# ninja_star.net
KiCad netlist of a schematic drawn in EAGLE
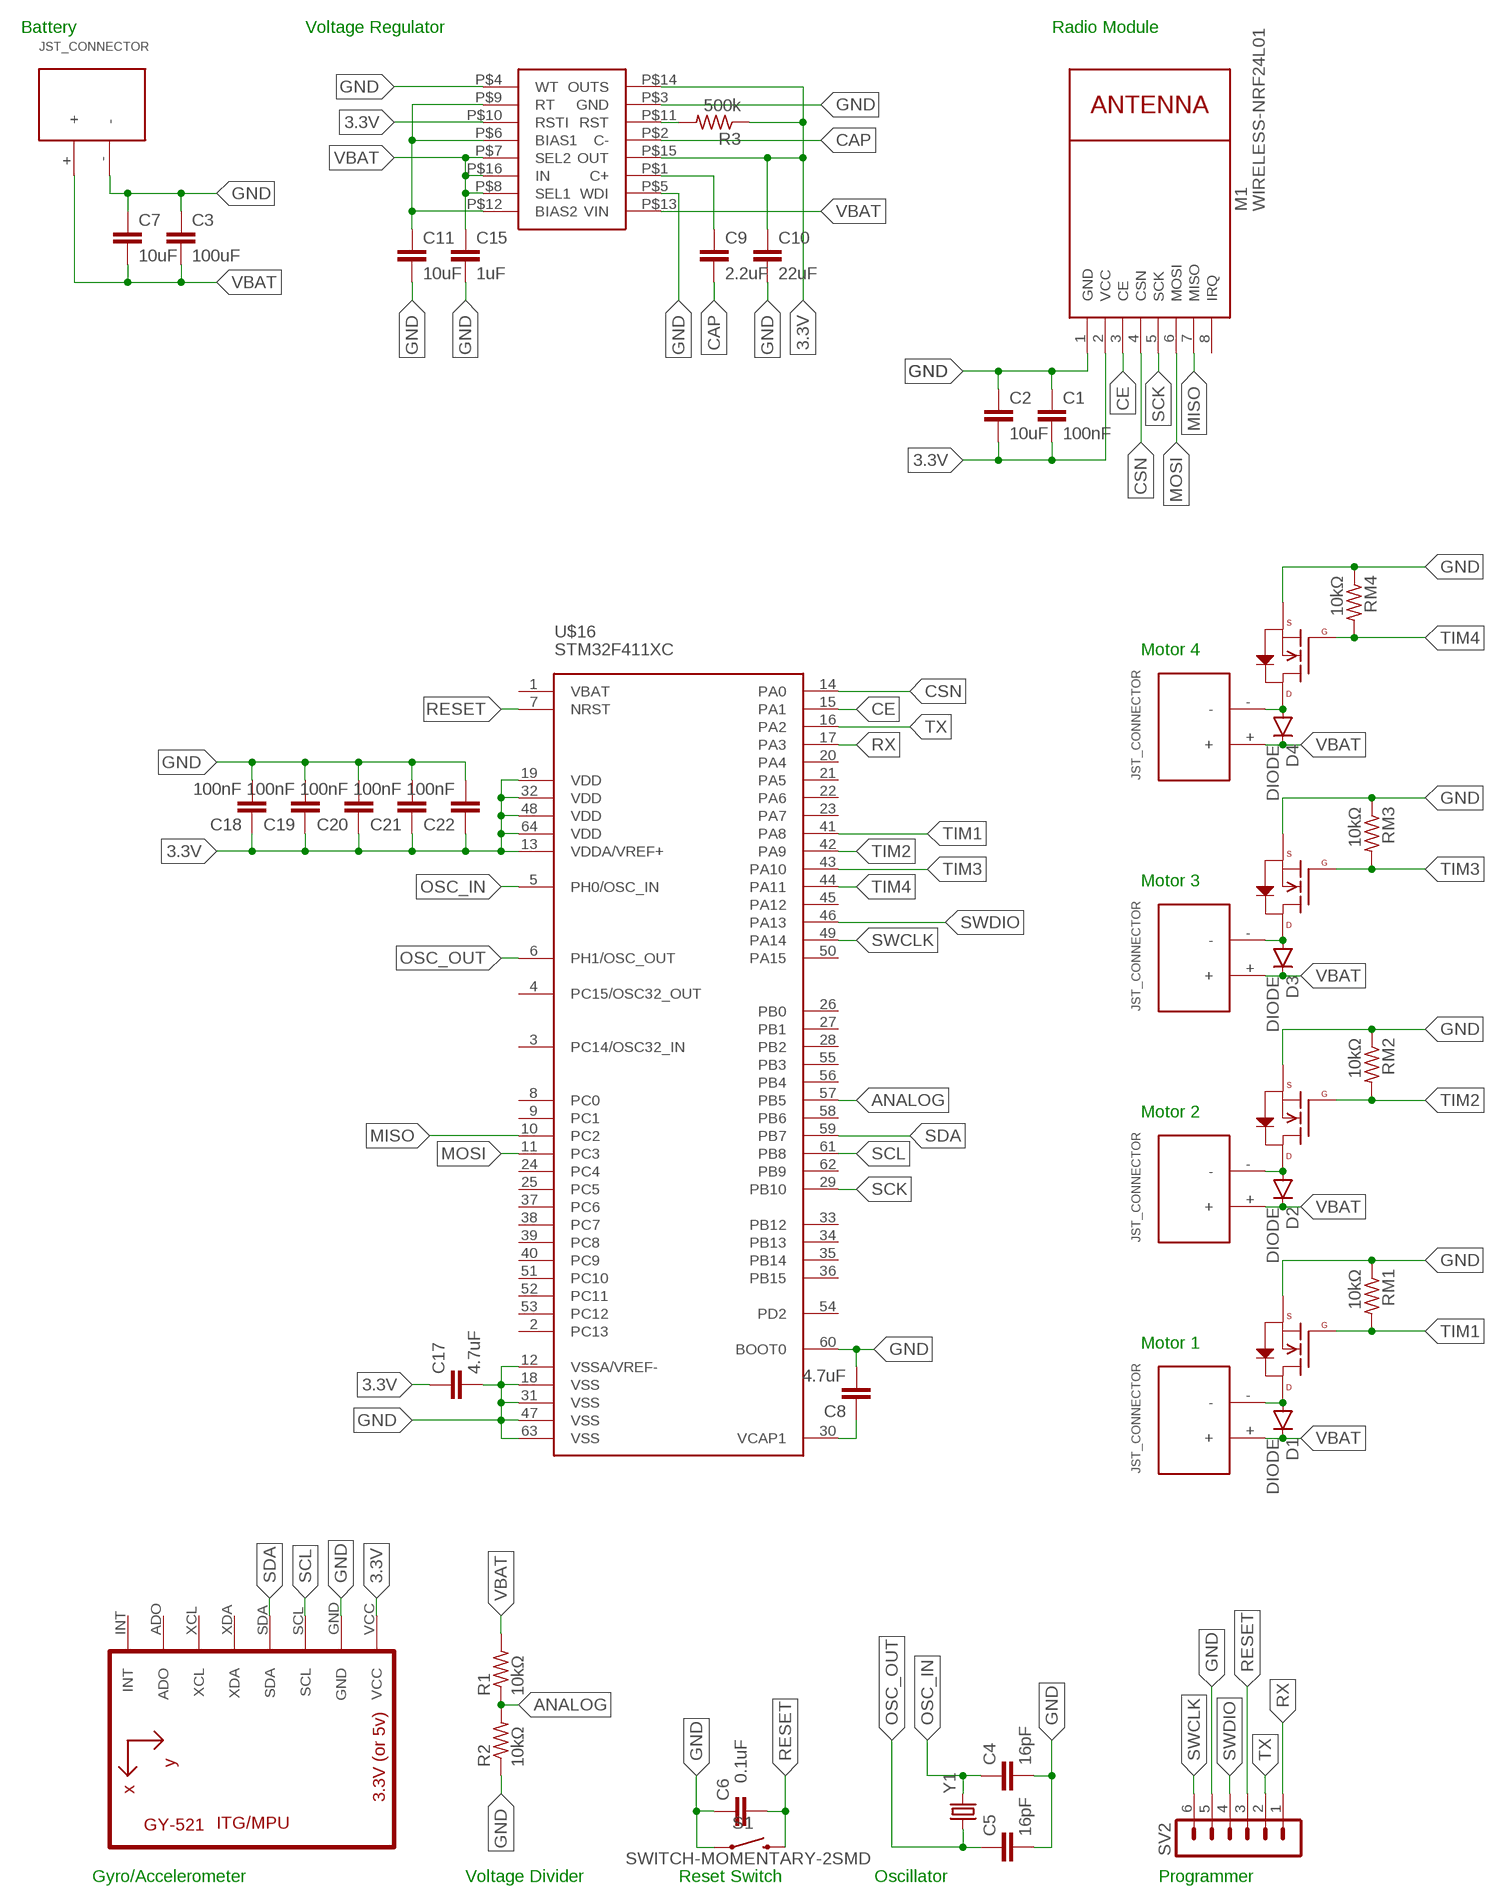
[diagram p0: schematic, sheet 1]

(export (version "E")
  (design (tool "Eeschema 10.0.6"))
  (components
    (comp (ref "C1")
      (value "100nF")
      (footprint "eagle-import:C0603")
      (libsource (lib "eagle-import") (part "C-EUC0603"))
    )
    (comp (ref "C2")
      (value "10uF")
      (footprint "eagle-import:C0603")
      (libsource (lib "eagle-import") (part "C-EUC0603"))
    )
    (comp (ref "C3")
      (value "100uF")
      (footprint "eagle-import:C1206")
      (libsource (lib "eagle-import") (part "C-EUC1206"))
    )
    (comp (ref "C4")
      (value "16pF")
      (footprint "eagle-import:C0603")
      (libsource (lib "eagle-import") (part "C-EUC0603"))
    )
    (comp (ref "C5")
      (value "16pF")
      (footprint "eagle-import:C0603")
      (libsource (lib "eagle-import") (part "C-EUC0603"))
    )
    (comp (ref "C6")
      (value "0.1uF")
      (footprint "eagle-import:C0603")
      (libsource (lib "eagle-import") (part "C-EUC0603"))
    )
    (comp (ref "C7")
      (value "10uF")
      (footprint "eagle-import:C0603")
      (libsource (lib "eagle-import") (part "C-EUC0603"))
    )
    (comp (ref "C8")
      (value "4.7uF")
      (footprint "eagle-import:C0603")
      (libsource (lib "eagle-import") (part "C-EUC0603"))
    )
    (comp (ref "C9")
      (value "2.2uF")
      (footprint "eagle-import:C0603")
      (libsource (lib "eagle-import") (part "C-EUC0603"))
    )
    (comp (ref "C10")
      (value "22uF")
      (footprint "eagle-import:C0603")
      (libsource (lib "eagle-import") (part "C-EUC0603"))
    )
    (comp (ref "C11")
      (value "10uF")
      (footprint "eagle-import:C0603")
      (libsource (lib "eagle-import") (part "C-EUC0603"))
    )
    (comp (ref "C15")
      (value "1uF")
      (footprint "eagle-import:C0603")
      (libsource (lib "eagle-import") (part "C-EUC0603"))
    )
    (comp (ref "C17")
      (value "4.7uF")
      (footprint "eagle-import:C0603")
      (libsource (lib "eagle-import") (part "C-EUC0603"))
    )
    (comp (ref "C18")
      (value "100nF")
      (footprint "eagle-import:C0603")
      (libsource (lib "eagle-import") (part "C-EUC0603"))
    )
    (comp (ref "C19")
      (value "100nF")
      (footprint "eagle-import:C0603")
      (libsource (lib "eagle-import") (part "C-EUC0603"))
    )
    (comp (ref "C20")
      (value "100nF")
      (footprint "eagle-import:C0603")
      (libsource (lib "eagle-import") (part "C-EUC0603"))
    )
    (comp (ref "C21")
      (value "100nF")
      (footprint "eagle-import:C0603")
      (libsource (lib "eagle-import") (part "C-EUC0603"))
    )
    (comp (ref "C22")
      (value "100nF")
      (footprint "eagle-import:C0603")
      (libsource (lib "eagle-import") (part "C-EUC0603"))
    )
    (comp (ref "D1")
      (value "DIODE")
      (footprint "eagle-import:C0603")
      (libsource (lib "eagle-import") (part "DIODE"))
    )
    (comp (ref "D2")
      (value "DIODE")
      (footprint "eagle-import:C0603")
      (libsource (lib "eagle-import") (part "DIODE"))
    )
    (comp (ref "D3")
      (value "DIODE")
      (footprint "eagle-import:C0603")
      (libsource (lib "eagle-import") (part "DIODE"))
    )
    (comp (ref "D4")
      (value "DIODE")
      (footprint "eagle-import:C0603")
      (libsource (lib "eagle-import") (part "DIODE"))
    )
    (comp (ref "M1")
      (value "WIRELESS-NRF24L01")
      (footprint "eagle-import:WIRELESS-NRF24L01")
      (libsource (lib "eagle-import") (part "WIRELESS-NRF24L01"))
    )
    (comp (ref "MOS1")
      (value "N-CHANNEL-MOSFET-IRLML6244TRPBF")
      (footprint "eagle-import:SOT23-3")
      (libsource (lib "eagle-import") (part "N-CHANNEL-MOSFET-IRLML6244TRPBF"))
    )
    (comp (ref "MOS2")
      (value "N-CHANNEL-MOSFET-IRLML6244TRPBF")
      (footprint "eagle-import:SOT23-3")
      (libsource (lib "eagle-import") (part "N-CHANNEL-MOSFET-IRLML6244TRPBF"))
    )
    (comp (ref "MOS3")
      (value "N-CHANNEL-MOSFET-IRLML6244TRPBF")
      (footprint "eagle-import:SOT23-3")
      (libsource (lib "eagle-import") (part "N-CHANNEL-MOSFET-IRLML6244TRPBF"))
    )
    (comp (ref "MOS4")
      (value "N-CHANNEL-MOSFET-IRLML6244TRPBF")
      (footprint "eagle-import:SOT23-3")
      (libsource (lib "eagle-import") (part "N-CHANNEL-MOSFET-IRLML6244TRPBF"))
    )
    (comp (ref "MOTOR1")
      (value "JST_CONNECTOR_FEMALE")
      (footprint "eagle-import:JST_CONNECTOR_FEMALE")
      (libsource (lib "eagle-import") (part "JST_CONNECTOR_FEMALE"))
    )
    (comp (ref "MOTOR2")
      (value "JST_CONNECTOR_FEMALE")
      (footprint "eagle-import:JST_CONNECTOR_FEMALE")
      (libsource (lib "eagle-import") (part "JST_CONNECTOR_FEMALE"))
    )
    (comp (ref "MOTOR3")
      (value "JST_CONNECTOR_FEMALE")
      (footprint "eagle-import:JST_CONNECTOR_FEMALE")
      (libsource (lib "eagle-import") (part "JST_CONNECTOR_FEMALE"))
    )
    (comp (ref "MOTOR4")
      (value "JST_CONNECTOR_FEMALE")
      (footprint "eagle-import:JST_CONNECTOR_FEMALE")
      (libsource (lib "eagle-import") (part "JST_CONNECTOR_FEMALE"))
    )
    (comp (ref "R1")
      (value "10kΩ")
      (footprint "eagle-import:R0603")
      (libsource (lib "eagle-import") (part "R-US_R0603"))
    )
    (comp (ref "R2")
      (value "10kΩ")
      (footprint "eagle-import:R0603")
      (libsource (lib "eagle-import") (part "R-US_R0603"))
    )
    (comp (ref "R3")
      (value "500k")
      (footprint "eagle-import:R0603")
      (libsource (lib "eagle-import") (part "R-0603"))
    )
    (comp (ref "RM1")
      (value "10kΩ")
      (footprint "eagle-import:R0603")
      (libsource (lib "eagle-import") (part "AP_quad_updated_R-0603"))
    )
    (comp (ref "RM2")
      (value "10kΩ")
      (footprint "eagle-import:R0603")
      (libsource (lib "eagle-import") (part "AP_quad_updated_R-0603"))
    )
    (comp (ref "RM3")
      (value "10kΩ")
      (footprint "eagle-import:R0603")
      (libsource (lib "eagle-import") (part "AP_quad_updated_R-0603"))
    )
    (comp (ref "RM4")
      (value "10kΩ")
      (footprint "eagle-import:R0603")
      (libsource (lib "eagle-import") (part "AP_quad_updated_R-0603"))
    )
    (comp (ref "S1")
      (value "SWITCH-MOMENTARY-2SMD")
      (footprint "eagle-import:TACTILE-SWITCH-SMD")
      (libsource (lib "eagle-import") (part "SWITCH-MOMENTARY-2SMD"))
    )
    (comp (ref "SV2")
      (value "MA06-1")
      (footprint "eagle-import:MA06-1")
      (libsource (lib "eagle-import") (part "MA06-1"))
    )
    (comp (ref "U$7")
      (value "JST_CONNECTOR_FEMALE")
      (footprint "eagle-import:JST_CONNECTOR_FEMALE")
      (libsource (lib "eagle-import") (part "JST_CONNECTOR_FEMALE"))
    )
    (comp (ref "U$12")
      (value "VR-LTC3246")
      (footprint "eagle-import:MSOP-16")
      (libsource (lib "eagle-import") (part "VR-LTC3246"))
    )
    (comp (ref "U$16")
      (value "STM32F411XC")
      (footprint "eagle-import:LQFP64")
      (libsource (lib "eagle-import") (part "STM32F411XC"))
    )
    (comp (ref "U1")
      (value "GY-521MPU6050")
      (footprint "eagle-import:GY-521")
      (libsource (lib "eagle-import") (part "GY-521MPU6050"))
    )
    (comp (ref "Y1")
      (value "CRYSTALHC49US")
      (footprint "eagle-import:HC49US")
      (libsource (lib "eagle-import") (part "CRYSTALHC49US"))
    )
  )
  (nets
    (net (code "1") (name "3.3V") (class "Default")
      (node (ref "C1") (pin "2") (pinfunction "2_2") (pintype "passive"))
      (node (ref "C10") (pin "1") (pinfunction "1_1") (pintype "passive"))
      (node (ref "C17") (pin "1") (pinfunction "1_1") (pintype "passive"))
      (node (ref "C18") (pin "1") (pinfunction "1_1") (pintype "passive"))
      (node (ref "C19") (pin "1") (pinfunction "1_1") (pintype "passive"))
      (node (ref "C2") (pin "2") (pinfunction "2_2") (pintype "passive"))
      (node (ref "C20") (pin "1") (pinfunction "1_1") (pintype "passive"))
      (node (ref "C21") (pin "1") (pinfunction "1_1") (pintype "passive"))
      (node (ref "C22") (pin "1") (pinfunction "1_1") (pintype "passive"))
      (node (ref "M1") (pin "2") (pinfunction "VCC_2") (pintype "power_in"))
      (node (ref "R3") (pin "1") (pinfunction "1_1") (pintype "passive"))
      (node (ref "U$12") (pin "P$10") (pinfunction "RSTI_P$10") (pintype "bidirectional"))
      (node (ref "U$12") (pin "P$14") (pinfunction "OUTS_P$14") (pintype "bidirectional"))
      (node (ref "U$12") (pin "P$15") (pinfunction "OUT_P$15") (pintype "bidirectional"))
      (node (ref "U$16") (pin "13") (pinfunction "VDDA/VREF+_13") (pintype "bidirectional"))
      (node (ref "U$16") (pin "19") (pinfunction "VDD_19") (pintype "bidirectional"))
      (node (ref "U$16") (pin "32") (pinfunction "VDD_32") (pintype "bidirectional"))
      (node (ref "U$16") (pin "48") (pinfunction "VDD_48") (pintype "bidirectional"))
      (node (ref "U$16") (pin "64") (pinfunction "VDD_64") (pintype "bidirectional"))
      (node (ref "U1") (pin "VCC") (pinfunction "VCC_VCC") (pintype "bidirectional"))
    )
    (net (code "2") (name "ANALOG") (class "Default")
      (node (ref "R1") (pin "1") (pinfunction "1_1") (pintype "passive"))
      (node (ref "R2") (pin "2") (pinfunction "2_2") (pintype "passive"))
      (node (ref "U$16") (pin "57") (pinfunction "PB5_57") (pintype "bidirectional"))
    )
    (net (code "3") (name "CAP") (class "Default")
      (node (ref "C9") (pin "2") (pinfunction "2_2") (pintype "passive"))
      (node (ref "U$12") (pin "P$2") (pinfunction "C-_P$2") (pintype "bidirectional"))
    )
    (net (code "4") (name "CE") (class "Default")
      (node (ref "M1") (pin "3") (pinfunction "CE_3") (pintype "bidirectional"))
      (node (ref "U$16") (pin "15") (pinfunction "PA1_15") (pintype "bidirectional"))
    )
    (net (code "5") (name "CSN") (class "Default")
      (node (ref "M1") (pin "4") (pinfunction "CSN_4") (pintype "bidirectional"))
      (node (ref "U$16") (pin "14") (pinfunction "PA0_14") (pintype "bidirectional"))
    )
    (net (code "6") (name "GND") (class "Default")
      (node (ref "C1") (pin "1") (pinfunction "1_1") (pintype "passive"))
      (node (ref "C10") (pin "2") (pinfunction "2_2") (pintype "passive"))
      (node (ref "C11") (pin "2") (pinfunction "2_2") (pintype "passive"))
      (node (ref "C15") (pin "2") (pinfunction "2_2") (pintype "passive"))
      (node (ref "C17") (pin "2") (pinfunction "2_2") (pintype "passive"))
      (node (ref "C18") (pin "2") (pinfunction "2_2") (pintype "passive"))
      (node (ref "C19") (pin "2") (pinfunction "2_2") (pintype "passive"))
      (node (ref "C2") (pin "1") (pinfunction "1_1") (pintype "passive"))
      (node (ref "C20") (pin "2") (pinfunction "2_2") (pintype "passive"))
      (node (ref "C21") (pin "2") (pinfunction "2_2") (pintype "passive"))
      (node (ref "C22") (pin "2") (pinfunction "2_2") (pintype "passive"))
      (node (ref "C3") (pin "1") (pinfunction "1_1") (pintype "passive"))
      (node (ref "C4") (pin "2") (pinfunction "2_2") (pintype "passive"))
      (node (ref "C5") (pin "2") (pinfunction "2_2") (pintype "passive"))
      (node (ref "C6") (pin "1") (pinfunction "1_1") (pintype "passive"))
      (node (ref "C7") (pin "1") (pinfunction "1_1") (pintype "passive"))
      (node (ref "C8") (pin "2") (pinfunction "2_2") (pintype "passive"))
      (node (ref "M1") (pin "1") (pinfunction "GND_1") (pintype "power_in"))
      (node (ref "MOS1") (pin "2") (pinfunction "S_2") (pintype "passive"))
      (node (ref "MOS2") (pin "2") (pinfunction "S_2") (pintype "passive"))
      (node (ref "MOS3") (pin "2") (pinfunction "S_2") (pintype "passive"))
      (node (ref "MOS4") (pin "2") (pinfunction "S_2") (pintype "passive"))
      (node (ref "R2") (pin "1") (pinfunction "1_1") (pintype "passive"))
      (node (ref "RM1") (pin "1") (pinfunction "1_1") (pintype "passive"))
      (node (ref "RM2") (pin "1") (pinfunction "1_1") (pintype "passive"))
      (node (ref "RM3") (pin "1") (pinfunction "1_1") (pintype "passive"))
      (node (ref "RM4") (pin "1") (pinfunction "1_1") (pintype "passive"))
      (node (ref "S1") (pin "1") (pinfunction "1_1") (pintype "passive"))
      (node (ref "SV2") (pin "5") (pinfunction "5_5") (pintype "passive"))
      (node (ref "U$12") (pin "P$3") (pinfunction "GND_P$3") (pintype "bidirectional"))
      (node (ref "U$12") (pin "P$4") (pinfunction "WT_P$4") (pintype "bidirectional"))
      (node (ref "U$12") (pin "P$5") (pinfunction "WDI_P$5") (pintype "bidirectional"))
      (node (ref "U$16") (pin "12") (pinfunction "VSSA/VREF-_12") (pintype "bidirectional"))
      (node (ref "U$16") (pin "18") (pinfunction "VSS_18") (pintype "bidirectional"))
      (node (ref "U$16") (pin "31") (pinfunction "VSS_31") (pintype "bidirectional"))
      (node (ref "U$16") (pin "47") (pinfunction "VSS_47") (pintype "bidirectional"))
      (node (ref "U$16") (pin "60") (pinfunction "BOOT0_60") (pintype "bidirectional"))
      (node (ref "U$16") (pin "63") (pinfunction "VSS_63") (pintype "bidirectional"))
      (node (ref "U$7") (pin "-") (pinfunction "-_-") (pintype "bidirectional"))
      (node (ref "U1") (pin "GND") (pinfunction "GND_GND") (pintype "bidirectional"))
    )
    (net (code "7") (name "MISO") (class "Default")
      (node (ref "M1") (pin "7") (pinfunction "MISO_7") (pintype "bidirectional"))
      (node (ref "U$16") (pin "10") (pinfunction "PC2_10") (pintype "bidirectional"))
    )
    (net (code "8") (name "MOSI") (class "Default")
      (node (ref "M1") (pin "6") (pinfunction "MOSI_6") (pintype "bidirectional"))
      (node (ref "U$16") (pin "11") (pinfunction "PC3_11") (pintype "bidirectional"))
    )
    (net (code "9") (name "Net-(D1-PPIN)") (class "Default")
      (node (ref "D1") (pin "2") (pinfunction "PPIN_2") (pintype "passive"))
      (node (ref "MOS1") (pin "3") (pinfunction "D_3") (pintype "passive"))
      (node (ref "MOTOR1") (pin "-") (pinfunction "-_-") (pintype "bidirectional"))
    )
    (net (code "10") (name "Net-(D2-PPIN)") (class "Default")
      (node (ref "D2") (pin "2") (pinfunction "PPIN_2") (pintype "passive"))
      (node (ref "MOS2") (pin "3") (pinfunction "D_3") (pintype "passive"))
      (node (ref "MOTOR2") (pin "-") (pinfunction "-_-") (pintype "bidirectional"))
    )
    (net (code "11") (name "Net-(D3-PPIN)") (class "Default")
      (node (ref "D3") (pin "2") (pinfunction "PPIN_2") (pintype "passive"))
      (node (ref "MOS3") (pin "3") (pinfunction "D_3") (pintype "passive"))
      (node (ref "MOTOR3") (pin "-") (pinfunction "-_-") (pintype "bidirectional"))
    )
    (net (code "12") (name "Net-(D4-PPIN)") (class "Default")
      (node (ref "D4") (pin "2") (pinfunction "PPIN_2") (pintype "passive"))
      (node (ref "MOS4") (pin "3") (pinfunction "D_3") (pintype "passive"))
      (node (ref "MOTOR4") (pin "-") (pinfunction "-_-") (pintype "bidirectional"))
    )
    (net (code "13") (name "Net-(U$12-BIAS1)") (class "Default")
      (node (ref "C11") (pin "1") (pinfunction "1_1") (pintype "passive"))
      (node (ref "U$12") (pin "P$12") (pinfunction "BIAS2_P$12") (pintype "bidirectional"))
      (node (ref "U$12") (pin "P$6") (pinfunction "BIAS1_P$6") (pintype "bidirectional"))
      (node (ref "U$12") (pin "P$9") (pinfunction "RT_P$9") (pintype "bidirectional"))
    )
    (net (code "14") (name "Net-(U$12-C+)") (class "Default")
      (node (ref "C9") (pin "1") (pinfunction "1_1") (pintype "passive"))
      (node (ref "U$12") (pin "P$1") (pinfunction "C+_P$1") (pintype "bidirectional"))
    )
    (net (code "15") (name "Net-(U$12-RST)") (class "Default")
      (node (ref "R3") (pin "2") (pinfunction "2_2") (pintype "passive"))
      (node (ref "U$12") (pin "P$11") (pinfunction "RST_P$11") (pintype "bidirectional"))
    )
    (net (code "16") (name "Net-(U$16-VCAP1)") (class "Default")
      (node (ref "C8") (pin "1") (pinfunction "1_1") (pintype "passive"))
      (node (ref "U$16") (pin "30") (pinfunction "VCAP1_30") (pintype "bidirectional"))
    )
    (net (code "17") (name "OSC_IN") (class "Default")
      (node (ref "C4") (pin "1") (pinfunction "1_1") (pintype "passive"))
      (node (ref "U$16") (pin "5") (pinfunction "PH0/OSC_IN_5") (pintype "bidirectional"))
      (node (ref "Y1") (pin "2") (pinfunction "2_2") (pintype "passive"))
    )
    (net (code "18") (name "OSC_OUT") (class "Default")
      (node (ref "C5") (pin "1") (pinfunction "1_1") (pintype "passive"))
      (node (ref "U$16") (pin "6") (pinfunction "PH1/OSC_OUT_6") (pintype "bidirectional"))
      (node (ref "Y1") (pin "1") (pinfunction "1_1") (pintype "passive"))
    )
    (net (code "19") (name "RESET") (class "Default")
      (node (ref "C6") (pin "2") (pinfunction "2_2") (pintype "passive"))
      (node (ref "S1") (pin "3") (pinfunction "2_3") (pintype "passive"))
      (node (ref "SV2") (pin "3") (pinfunction "3_3") (pintype "passive"))
      (node (ref "U$16") (pin "7") (pinfunction "NRST_7") (pintype "bidirectional"))
    )
    (net (code "20") (name "RX") (class "Default")
      (node (ref "SV2") (pin "1") (pinfunction "1_1") (pintype "passive"))
      (node (ref "U$16") (pin "17") (pinfunction "PA3_17") (pintype "bidirectional"))
    )
    (net (code "21") (name "SCK") (class "Default")
      (node (ref "M1") (pin "5") (pinfunction "SCK_5") (pintype "bidirectional"))
      (node (ref "U$16") (pin "29") (pinfunction "PB10_29") (pintype "bidirectional"))
    )
    (net (code "22") (name "SCL") (class "Default")
      (node (ref "U$16") (pin "61") (pinfunction "PB8_61") (pintype "bidirectional"))
      (node (ref "U1") (pin "SCL") (pinfunction "SCL_SCL") (pintype "bidirectional"))
    )
    (net (code "23") (name "SDA") (class "Default")
      (node (ref "U$16") (pin "59") (pinfunction "PB7_59") (pintype "bidirectional"))
      (node (ref "U1") (pin "SDA") (pinfunction "SDA_SDA") (pintype "bidirectional"))
    )
    (net (code "24") (name "SWCLK") (class "Default")
      (node (ref "SV2") (pin "6") (pinfunction "6_6") (pintype "passive"))
      (node (ref "U$16") (pin "49") (pinfunction "PA14_49") (pintype "bidirectional"))
    )
    (net (code "25") (name "SWDIO") (class "Default")
      (node (ref "SV2") (pin "4") (pinfunction "4_4") (pintype "passive"))
      (node (ref "U$16") (pin "46") (pinfunction "PA13_46") (pintype "bidirectional"))
    )
    (net (code "26") (name "TIM1") (class "Default")
      (node (ref "MOS1") (pin "1") (pinfunction "G_1") (pintype "passive"))
      (node (ref "RM1") (pin "2") (pinfunction "2_2") (pintype "passive"))
      (node (ref "U$16") (pin "41") (pinfunction "PA8_41") (pintype "bidirectional"))
    )
    (net (code "27") (name "TIM2") (class "Default")
      (node (ref "MOS2") (pin "1") (pinfunction "G_1") (pintype "passive"))
      (node (ref "RM2") (pin "2") (pinfunction "2_2") (pintype "passive"))
      (node (ref "U$16") (pin "42") (pinfunction "PA9_42") (pintype "bidirectional"))
    )
    (net (code "28") (name "TIM3") (class "Default")
      (node (ref "MOS3") (pin "1") (pinfunction "G_1") (pintype "passive"))
      (node (ref "RM3") (pin "2") (pinfunction "2_2") (pintype "passive"))
      (node (ref "U$16") (pin "43") (pinfunction "PA10_43") (pintype "bidirectional"))
    )
    (net (code "29") (name "TIM4") (class "Default")
      (node (ref "MOS4") (pin "1") (pinfunction "G_1") (pintype "passive"))
      (node (ref "RM4") (pin "2") (pinfunction "2_2") (pintype "passive"))
      (node (ref "U$16") (pin "44") (pinfunction "PA11_44") (pintype "bidirectional"))
    )
    (net (code "30") (name "TX") (class "Default")
      (node (ref "SV2") (pin "2") (pinfunction "2_2") (pintype "passive"))
      (node (ref "U$16") (pin "16") (pinfunction "PA2_16") (pintype "bidirectional"))
    )
    (net (code "31") (name "VBAT") (class "Default")
      (node (ref "C15") (pin "1") (pinfunction "1_1") (pintype "passive"))
      (node (ref "C3") (pin "2") (pinfunction "2_2") (pintype "passive"))
      (node (ref "C7") (pin "2") (pinfunction "2_2") (pintype "passive"))
      (node (ref "D1") (pin "1") (pinfunction "GPIN_1") (pintype "passive"))
      (node (ref "D2") (pin "1") (pinfunction "GPIN_1") (pintype "passive"))
      (node (ref "D3") (pin "1") (pinfunction "GPIN_1") (pintype "passive"))
      (node (ref "D4") (pin "1") (pinfunction "GPIN_1") (pintype "passive"))
      (node (ref "MOTOR1") (pin "+") (pinfunction "+_+") (pintype "bidirectional"))
      (node (ref "MOTOR2") (pin "+") (pinfunction "+_+") (pintype "bidirectional"))
      (node (ref "MOTOR3") (pin "+") (pinfunction "+_+") (pintype "bidirectional"))
      (node (ref "MOTOR4") (pin "+") (pinfunction "+_+") (pintype "bidirectional"))
      (node (ref "R1") (pin "2") (pinfunction "2_2") (pintype "passive"))
      (node (ref "U$12") (pin "P$13") (pinfunction "VIN_P$13") (pintype "bidirectional"))
      (node (ref "U$12") (pin "P$16") (pinfunction "IN_P$16") (pintype "bidirectional"))
      (node (ref "U$12") (pin "P$7") (pinfunction "SEL2_P$7") (pintype "bidirectional"))
      (node (ref "U$12") (pin "P$8") (pinfunction "SEL1_P$8") (pintype "bidirectional"))
      (node (ref "U$7") (pin "+") (pinfunction "+_+") (pintype "bidirectional"))
    )
    (net (code "32") (name "unconnected-(M1-IRQ-Pad8)") (class "Default")
      (node (ref "M1") (pin "8") (pinfunction "IRQ_8") (pintype "bidirectional"))
    )
    (net (code "33") (name "unconnected-(U$16-PA4-Pad20)") (class "Default")
      (node (ref "U$16") (pin "20") (pinfunction "PA4_20") (pintype "bidirectional"))
    )
    (net (code "34") (name "unconnected-(U$16-PA5-Pad21)") (class "Default")
      (node (ref "U$16") (pin "21") (pinfunction "PA5_21") (pintype "bidirectional"))
    )
    (net (code "35") (name "unconnected-(U$16-PA6-Pad22)") (class "Default")
      (node (ref "U$16") (pin "22") (pinfunction "PA6_22") (pintype "bidirectional"))
    )
    (net (code "36") (name "unconnected-(U$16-PA7-Pad23)") (class "Default")
      (node (ref "U$16") (pin "23") (pinfunction "PA7_23") (pintype "bidirectional"))
    )
    (net (code "37") (name "unconnected-(U$16-PA12-Pad45)") (class "Default")
      (node (ref "U$16") (pin "45") (pinfunction "PA12_45") (pintype "bidirectional"))
    )
    (net (code "38") (name "unconnected-(U$16-PA15-Pad50)") (class "Default")
      (node (ref "U$16") (pin "50") (pinfunction "PA15_50") (pintype "bidirectional"))
    )
    (net (code "39") (name "unconnected-(U$16-PB0-Pad26)") (class "Default")
      (node (ref "U$16") (pin "26") (pinfunction "PB0_26") (pintype "bidirectional"))
    )
    (net (code "40") (name "unconnected-(U$16-PB1-Pad27)") (class "Default")
      (node (ref "U$16") (pin "27") (pinfunction "PB1_27") (pintype "bidirectional"))
    )
    (net (code "41") (name "unconnected-(U$16-PB2-Pad28)") (class "Default")
      (node (ref "U$16") (pin "28") (pinfunction "PB2_28") (pintype "bidirectional"))
    )
    (net (code "42") (name "unconnected-(U$16-PB3-Pad55)") (class "Default")
      (node (ref "U$16") (pin "55") (pinfunction "PB3_55") (pintype "bidirectional"))
    )
    (net (code "43") (name "unconnected-(U$16-PB4-Pad56)") (class "Default")
      (node (ref "U$16") (pin "56") (pinfunction "PB4_56") (pintype "bidirectional"))
    )
    (net (code "44") (name "unconnected-(U$16-PB6-Pad58)") (class "Default")
      (node (ref "U$16") (pin "58") (pinfunction "PB6_58") (pintype "bidirectional"))
    )
    (net (code "45") (name "unconnected-(U$16-PB9-Pad62)") (class "Default")
      (node (ref "U$16") (pin "62") (pinfunction "PB9_62") (pintype "bidirectional"))
    )
    (net (code "46") (name "unconnected-(U$16-PB12-Pad33)") (class "Default")
      (node (ref "U$16") (pin "33") (pinfunction "PB12_33") (pintype "bidirectional"))
    )
    (net (code "47") (name "unconnected-(U$16-PB13-Pad34)") (class "Default")
      (node (ref "U$16") (pin "34") (pinfunction "PB13_34") (pintype "bidirectional"))
    )
    (net (code "48") (name "unconnected-(U$16-PB14-Pad35)") (class "Default")
      (node (ref "U$16") (pin "35") (pinfunction "PB14_35") (pintype "bidirectional"))
    )
    (net (code "49") (name "unconnected-(U$16-PB15-Pad36)") (class "Default")
      (node (ref "U$16") (pin "36") (pinfunction "PB15_36") (pintype "bidirectional"))
    )
    (net (code "50") (name "unconnected-(U$16-PC0-Pad8)") (class "Default")
      (node (ref "U$16") (pin "8") (pinfunction "PC0_8") (pintype "bidirectional"))
    )
    (net (code "51") (name "unconnected-(U$16-PC1-Pad9)") (class "Default")
      (node (ref "U$16") (pin "9") (pinfunction "PC1_9") (pintype "bidirectional"))
    )
    (net (code "52") (name "unconnected-(U$16-PC4-Pad24)") (class "Default")
      (node (ref "U$16") (pin "24") (pinfunction "PC4_24") (pintype "bidirectional"))
    )
    (net (code "53") (name "unconnected-(U$16-PC5-Pad25)") (class "Default")
      (node (ref "U$16") (pin "25") (pinfunction "PC5_25") (pintype "bidirectional"))
    )
    (net (code "54") (name "unconnected-(U$16-PC6-Pad37)") (class "Default")
      (node (ref "U$16") (pin "37") (pinfunction "PC6_37") (pintype "bidirectional"))
    )
    (net (code "55") (name "unconnected-(U$16-PC7-Pad38)") (class "Default")
      (node (ref "U$16") (pin "38") (pinfunction "PC7_38") (pintype "bidirectional"))
    )
    (net (code "56") (name "unconnected-(U$16-PC8-Pad39)") (class "Default")
      (node (ref "U$16") (pin "39") (pinfunction "PC8_39") (pintype "bidirectional"))
    )
    (net (code "57") (name "unconnected-(U$16-PC9-Pad40)") (class "Default")
      (node (ref "U$16") (pin "40") (pinfunction "PC9_40") (pintype "bidirectional"))
    )
    (net (code "58") (name "unconnected-(U$16-PC10-Pad51)") (class "Default")
      (node (ref "U$16") (pin "51") (pinfunction "PC10_51") (pintype "bidirectional"))
    )
    (net (code "59") (name "unconnected-(U$16-PC11-Pad52)") (class "Default")
      (node (ref "U$16") (pin "52") (pinfunction "PC11_52") (pintype "bidirectional"))
    )
    (net (code "60") (name "unconnected-(U$16-PC12-Pad53)") (class "Default")
      (node (ref "U$16") (pin "53") (pinfunction "PC12_53") (pintype "bidirectional"))
    )
    (net (code "61") (name "unconnected-(U$16-PC13-Pad2)") (class "Default")
      (node (ref "U$16") (pin "2") (pinfunction "PC13_2") (pintype "bidirectional"))
    )
    (net (code "62") (name "unconnected-(U$16-PC14{slash}OSC32_IN-Pad3)") (class "Default")
      (node (ref "U$16") (pin "3") (pinfunction "PC14/OSC32_IN_3") (pintype "bidirectional"))
    )
    (net (code "63") (name "unconnected-(U$16-PC15{slash}OSC32_OUT-Pad4)") (class "Default")
      (node (ref "U$16") (pin "4") (pinfunction "PC15/OSC32_OUT_4") (pintype "bidirectional"))
    )
    (net (code "64") (name "unconnected-(U$16-PD2-Pad54)") (class "Default")
      (node (ref "U$16") (pin "54") (pinfunction "PD2_54") (pintype "bidirectional"))
    )
    (net (code "65") (name "unconnected-(U$16-VBAT-Pad1)") (class "Default")
      (node (ref "U$16") (pin "1") (pinfunction "VBAT_1") (pintype "bidirectional"))
    )
    (net (code "66") (name "unconnected-(U1-PadADO)") (class "Default")
      (node (ref "U1") (pin "ADO") (pinfunction "ADO_ADO") (pintype "bidirectional"))
    )
    (net (code "67") (name "unconnected-(U1-PadINT)") (class "Default")
      (node (ref "U1") (pin "INT") (pinfunction "INT_INT") (pintype "bidirectional"))
    )
    (net (code "68") (name "unconnected-(U1-PadXCL)") (class "Default")
      (node (ref "U1") (pin "XCL") (pinfunction "XCL_XCL") (pintype "bidirectional"))
    )
    (net (code "69") (name "unconnected-(U1-PadXDA)") (class "Default")
      (node (ref "U1") (pin "XDA") (pinfunction "XDA_XDA") (pintype "bidirectional"))
    )
  )
)
